# LightingModule.net
KiCad netlist of a schematic drawn in EAGLE
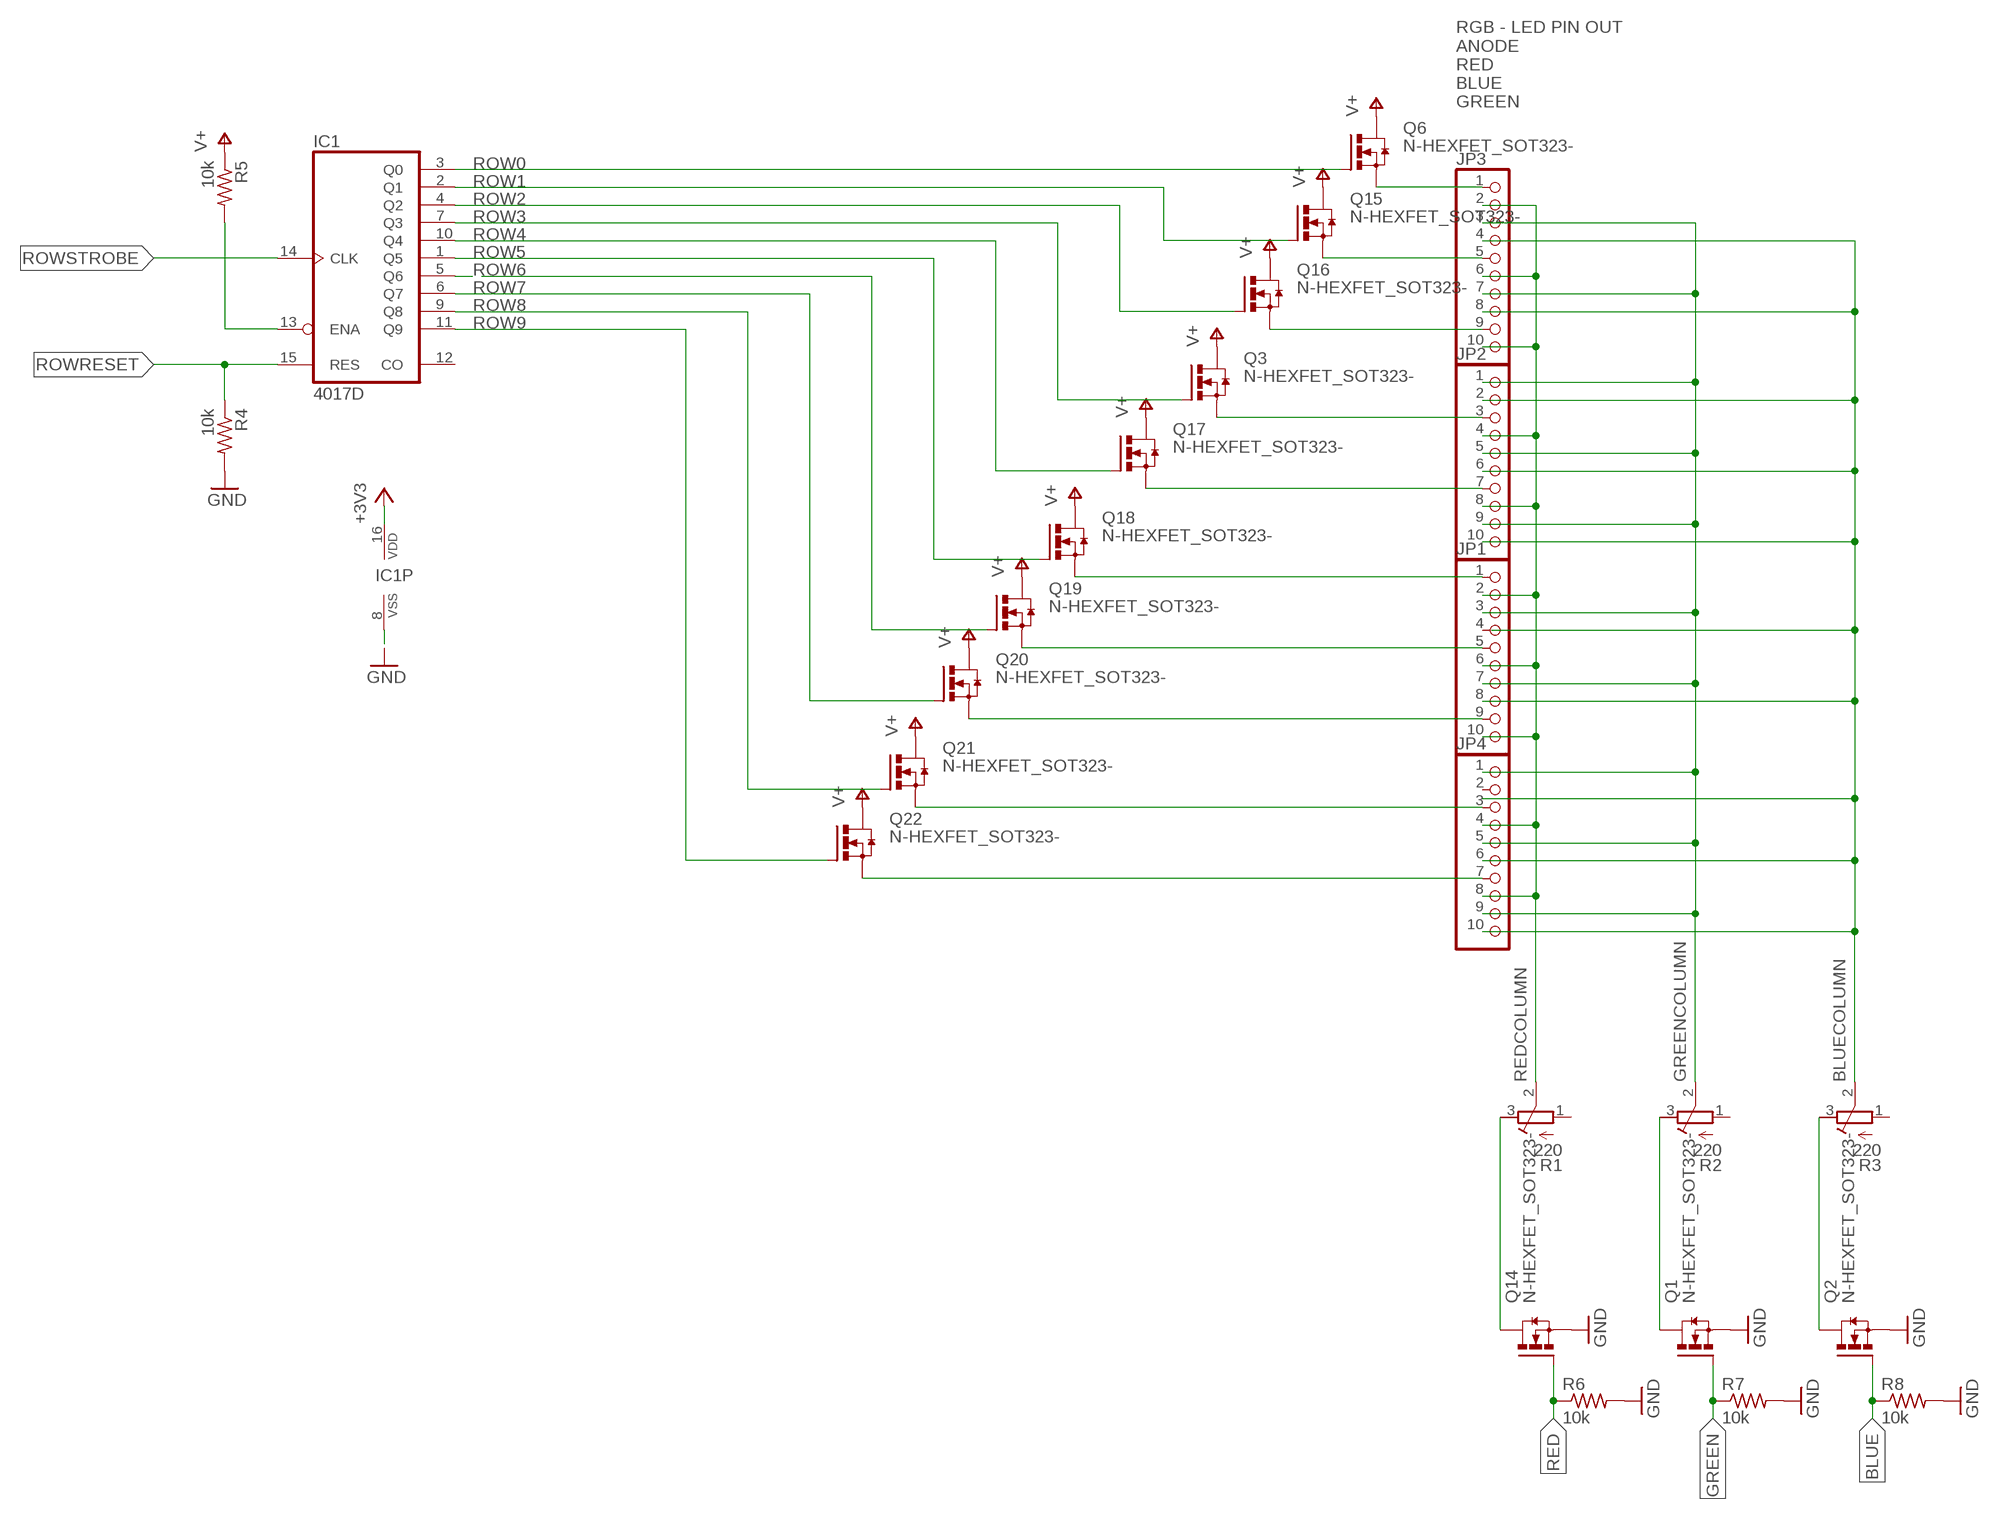
[diagram p0: schematic, sheet 1]

(export (version "E")
  (design (tool "Eeschema 10.0.6"))
  (components
    (comp (ref "IC1")
      (value "4017D")
      (footprint "eagle-import:SO16")
      (libsource (lib "eagle-import") (part "4017D"))
    )
    (comp (ref "JP1")
      (value "PINHD-1X10/90")
      (footprint "eagle-import:1X10_90")
      (libsource (lib "eagle-import") (part "PINHD-1X10/90"))
    )
    (comp (ref "JP2")
      (value "PINHD-1X10/90")
      (footprint "eagle-import:1X10_90")
      (libsource (lib "eagle-import") (part "PINHD-1X10/90"))
    )
    (comp (ref "JP3")
      (value "PINHD-1X10/90")
      (footprint "eagle-import:1X10_90")
      (libsource (lib "eagle-import") (part "PINHD-1X10/90"))
    )
    (comp (ref "JP4")
      (value "PINHD-1X10/90")
      (footprint "eagle-import:1X10_90")
      (libsource (lib "eagle-import") (part "PINHD-1X10/90"))
    )
    (comp (ref "Q1")
      (value "N-HEXFET_SOT323-")
      (footprint "eagle-import:SOT223")
      (libsource (lib "eagle-import") (part "N-HEXFET_?-SOT323"))
    )
    (comp (ref "Q2")
      (value "N-HEXFET_SOT323-")
      (footprint "eagle-import:SOT223")
      (libsource (lib "eagle-import") (part "N-HEXFET_?-SOT323"))
    )
    (comp (ref "Q3")
      (value "N-HEXFET_SOT323-")
      (footprint "eagle-import:SOT223")
      (libsource (lib "eagle-import") (part "N-HEXFET_?-SOT323"))
    )
    (comp (ref "Q6")
      (value "N-HEXFET_SOT323-")
      (footprint "eagle-import:SOT223")
      (libsource (lib "eagle-import") (part "N-HEXFET_?-SOT323"))
    )
    (comp (ref "Q14")
      (value "N-HEXFET_SOT323-")
      (footprint "eagle-import:SOT223")
      (libsource (lib "eagle-import") (part "N-HEXFET_?-SOT323"))
    )
    (comp (ref "Q15")
      (value "N-HEXFET_SOT323-")
      (footprint "eagle-import:SOT223")
      (libsource (lib "eagle-import") (part "N-HEXFET_?-SOT323"))
    )
    (comp (ref "Q16")
      (value "N-HEXFET_SOT323-")
      (footprint "eagle-import:SOT223")
      (libsource (lib "eagle-import") (part "N-HEXFET_?-SOT323"))
    )
    (comp (ref "Q17")
      (value "N-HEXFET_SOT323-")
      (footprint "eagle-import:SOT223")
      (libsource (lib "eagle-import") (part "N-HEXFET_?-SOT323"))
    )
    (comp (ref "Q18")
      (value "N-HEXFET_SOT323-")
      (footprint "eagle-import:SOT223")
      (libsource (lib "eagle-import") (part "N-HEXFET_?-SOT323"))
    )
    (comp (ref "Q19")
      (value "N-HEXFET_SOT323-")
      (footprint "eagle-import:SOT223")
      (libsource (lib "eagle-import") (part "N-HEXFET_?-SOT323"))
    )
    (comp (ref "Q20")
      (value "N-HEXFET_SOT323-")
      (footprint "eagle-import:SOT223")
      (libsource (lib "eagle-import") (part "N-HEXFET_?-SOT323"))
    )
    (comp (ref "Q21")
      (value "N-HEXFET_SOT323-")
      (footprint "eagle-import:SOT223")
      (libsource (lib "eagle-import") (part "N-HEXFET_?-SOT323"))
    )
    (comp (ref "Q22")
      (value "N-HEXFET_SOT323-")
      (footprint "eagle-import:SOT223")
      (libsource (lib "eagle-import") (part "N-HEXFET_?-SOT323"))
    )
    (comp (ref "R1")
      (value "220")
      (footprint "eagle-import:RTRIM3374")
      (libsource (lib "eagle-import") (part "R-TRIMM3374"))
    )
    (comp (ref "R2")
      (value "220")
      (footprint "eagle-import:RTRIM3374")
      (libsource (lib "eagle-import") (part "R-TRIMM3374"))
    )
    (comp (ref "R3")
      (value "220")
      (footprint "eagle-import:RTRIM3374")
      (libsource (lib "eagle-import") (part "R-TRIMM3374"))
    )
    (comp (ref "R4")
      (value "10k")
      (footprint "eagle-import:M0805")
      (libsource (lib "eagle-import") (part "R-US_M0805"))
    )
    (comp (ref "R5")
      (value "10k")
      (footprint "eagle-import:M0805")
      (libsource (lib "eagle-import") (part "R-US_M0805"))
    )
    (comp (ref "R6")
      (value "10k")
      (footprint "eagle-import:M0805")
      (libsource (lib "eagle-import") (part "R-US_M0805"))
    )
    (comp (ref "R7")
      (value "10k")
      (footprint "eagle-import:M0805")
      (libsource (lib "eagle-import") (part "R-US_M0805"))
    )
    (comp (ref "R8")
      (value "10k")
      (footprint "eagle-import:M0805")
      (libsource (lib "eagle-import") (part "R-US_M0805"))
    )
  )
  (nets
    (net (code "1") (name "+3V3") (class "Default")
      (node (ref "IC1") (pin "16") (pinfunction "VDD_16") (pintype "power_in"))
    )
    (net (code "2") (name "/BLUECOLUMN") (class "Default")
      (node (ref "JP1") (pin "8") (pinfunction "8_8") (pintype "passive"))
      (node (ref "JP2") (pin "10") (pinfunction "10_10") (pintype "passive"))
      (node (ref "JP2") (pin "2") (pinfunction "2_2") (pintype "passive"))
      (node (ref "JP2") (pin "6") (pinfunction "6_6") (pintype "passive"))
      (node (ref "JP3") (pin "4") (pinfunction "4_4") (pintype "passive"))
      (node (ref "JP3") (pin "8") (pinfunction "8_8") (pintype "passive"))
      (node (ref "JP4") (pin "10") (pinfunction "10_10") (pintype "passive"))
      (node (ref "JP4") (pin "6") (pinfunction "6_6") (pintype "passive"))
      (node (ref "R3") (pin "2") (pinfunction "S_2") (pintype "passive"))
    )
    (net (code "3") (name "/GREENCOLUMN") (class "Default")
      (node (ref "JP1") (pin "3") (pinfunction "3_3") (pintype "passive"))
      (node (ref "JP1") (pin "7") (pinfunction "7_7") (pintype "passive"))
      (node (ref "JP2") (pin "1") (pinfunction "1_1") (pintype "passive"))
      (node (ref "JP2") (pin "5") (pinfunction "5_5") (pintype "passive"))
      (node (ref "JP2") (pin "9") (pinfunction "9_9") (pintype "passive"))
      (node (ref "JP3") (pin "3") (pinfunction "3_3") (pintype "passive"))
      (node (ref "JP3") (pin "7") (pinfunction "7_7") (pintype "passive"))
      (node (ref "JP4") (pin "1") (pinfunction "1_1") (pintype "passive"))
      (node (ref "JP4") (pin "5") (pinfunction "5_5") (pintype "passive"))
      (node (ref "JP4") (pin "9") (pinfunction "9_9") (pintype "passive"))
      (node (ref "R2") (pin "2") (pinfunction "S_2") (pintype "passive"))
    )
    (net (code "4") (name "/REDCOLUMN") (class "Default")
      (node (ref "JP1") (pin "10") (pinfunction "10_10") (pintype "passive"))
      (node (ref "JP1") (pin "2") (pinfunction "2_2") (pintype "passive"))
      (node (ref "JP1") (pin "6") (pinfunction "6_6") (pintype "passive"))
      (node (ref "JP2") (pin "4") (pinfunction "4_4") (pintype "passive"))
      (node (ref "JP2") (pin "8") (pinfunction "8_8") (pintype "passive"))
      (node (ref "JP3") (pin "10") (pinfunction "10_10") (pintype "passive"))
      (node (ref "JP3") (pin "2") (pinfunction "2_2") (pintype "passive"))
      (node (ref "JP3") (pin "6") (pinfunction "6_6") (pintype "passive"))
      (node (ref "JP4") (pin "4") (pinfunction "4_4") (pintype "passive"))
      (node (ref "JP4") (pin "8") (pinfunction "8_8") (pintype "passive"))
      (node (ref "R1") (pin "2") (pinfunction "S_2") (pintype "passive"))
    )
    (net (code "5") (name "/ROW0") (class "Default")
      (node (ref "IC1") (pin "3") (pinfunction "Q0_3") (pintype "output"))
      (node (ref "Q6") (pin "1") (pinfunction "G_1") (pintype "passive"))
    )
    (net (code "6") (name "/ROW1") (class "Default")
      (node (ref "IC1") (pin "2") (pinfunction "Q1_2") (pintype "output"))
      (node (ref "Q15") (pin "1") (pinfunction "G_1") (pintype "passive"))
    )
    (net (code "7") (name "/ROW2") (class "Default")
      (node (ref "IC1") (pin "4") (pinfunction "Q2_4") (pintype "output"))
      (node (ref "Q16") (pin "1") (pinfunction "G_1") (pintype "passive"))
    )
    (net (code "8") (name "/ROW3") (class "Default")
      (node (ref "IC1") (pin "7") (pinfunction "Q3_7") (pintype "output"))
      (node (ref "Q3") (pin "1") (pinfunction "G_1") (pintype "passive"))
    )
    (net (code "9") (name "/ROW4") (class "Default")
      (node (ref "IC1") (pin "10") (pinfunction "Q4_10") (pintype "output"))
      (node (ref "Q17") (pin "1") (pinfunction "G_1") (pintype "passive"))
    )
    (net (code "10") (name "/ROW5") (class "Default")
      (node (ref "IC1") (pin "1") (pinfunction "Q5_1") (pintype "output"))
      (node (ref "Q18") (pin "1") (pinfunction "G_1") (pintype "passive"))
    )
    (net (code "11") (name "/ROW6") (class "Default")
      (node (ref "IC1") (pin "5") (pinfunction "Q6_5") (pintype "output"))
    )
    (net (code "12") (name "/ROW7") (class "Default")
      (node (ref "IC1") (pin "6") (pinfunction "Q7_6") (pintype "output"))
      (node (ref "Q20") (pin "1") (pinfunction "G_1") (pintype "passive"))
    )
    (net (code "13") (name "/ROW8") (class "Default")
      (node (ref "IC1") (pin "9") (pinfunction "Q8_9") (pintype "output"))
      (node (ref "Q21") (pin "1") (pinfunction "G_1") (pintype "passive"))
    )
    (net (code "14") (name "/ROW9") (class "Default")
      (node (ref "IC1") (pin "11") (pinfunction "Q9_11") (pintype "output"))
      (node (ref "Q22") (pin "1") (pinfunction "G_1") (pintype "passive"))
    )
    (net (code "15") (name "BLUE") (class "Default")
      (node (ref "Q2") (pin "1") (pinfunction "G_1") (pintype "passive"))
      (node (ref "R8") (pin "1") (pinfunction "1_1") (pintype "passive"))
    )
    (net (code "16") (name "GND") (class "Default")
      (node (ref "IC1") (pin "8") (pinfunction "VSS_8") (pintype "power_in"))
      (node (ref "Q1") (pin "3") (pinfunction "S_3") (pintype "passive"))
      (node (ref "Q14") (pin "3") (pinfunction "S_3") (pintype "passive"))
      (node (ref "Q2") (pin "3") (pinfunction "S_3") (pintype "passive"))
      (node (ref "R4") (pin "2") (pinfunction "2_2") (pintype "passive"))
      (node (ref "R6") (pin "2") (pinfunction "2_2") (pintype "passive"))
      (node (ref "R7") (pin "2") (pinfunction "2_2") (pintype "passive"))
      (node (ref "R8") (pin "2") (pinfunction "2_2") (pintype "passive"))
    )
    (net (code "17") (name "GREEN") (class "Default")
      (node (ref "Q1") (pin "1") (pinfunction "G_1") (pintype "passive"))
      (node (ref "R7") (pin "1") (pinfunction "1_1") (pintype "passive"))
    )
    (net (code "18") (name "Net-(IC1A-ENA)") (class "Default")
      (node (ref "IC1") (pin "13") (pinfunction "ENA_13") (pintype "input"))
      (node (ref "R5") (pin "2") (pinfunction "2_2") (pintype "passive"))
    )
    (net (code "19") (name "Net-(Q1-D)") (class "Default")
      (node (ref "Q1") (pin "4") (pinfunction "D_4") (pintype "passive"))
      (node (ref "R2") (pin "3") (pinfunction "A_3") (pintype "passive"))
    )
    (net (code "20") (name "Net-(Q2-D)") (class "Default")
      (node (ref "Q2") (pin "4") (pinfunction "D_4") (pintype "passive"))
      (node (ref "R3") (pin "3") (pinfunction "A_3") (pintype "passive"))
    )
    (net (code "21") (name "Net-(Q3-S)") (class "Default")
      (node (ref "JP2") (pin "3") (pinfunction "3_3") (pintype "passive"))
      (node (ref "Q3") (pin "3") (pinfunction "S_3") (pintype "passive"))
    )
    (net (code "22") (name "Net-(Q6-S)") (class "Default")
      (node (ref "JP3") (pin "1") (pinfunction "1_1") (pintype "passive"))
      (node (ref "Q6") (pin "3") (pinfunction "S_3") (pintype "passive"))
    )
    (net (code "23") (name "Net-(Q14-D)") (class "Default")
      (node (ref "Q14") (pin "4") (pinfunction "D_4") (pintype "passive"))
      (node (ref "R1") (pin "3") (pinfunction "A_3") (pintype "passive"))
    )
    (net (code "24") (name "Net-(Q15-S)") (class "Default")
      (node (ref "JP3") (pin "5") (pinfunction "5_5") (pintype "passive"))
      (node (ref "Q15") (pin "3") (pinfunction "S_3") (pintype "passive"))
    )
    (net (code "25") (name "Net-(Q16-S)") (class "Default")
      (node (ref "JP3") (pin "9") (pinfunction "9_9") (pintype "passive"))
      (node (ref "Q16") (pin "3") (pinfunction "S_3") (pintype "passive"))
    )
    (net (code "26") (name "Net-(Q17-S)") (class "Default")
      (node (ref "JP2") (pin "7") (pinfunction "7_7") (pintype "passive"))
      (node (ref "Q17") (pin "3") (pinfunction "S_3") (pintype "passive"))
    )
    (net (code "27") (name "Net-(Q18-S)") (class "Default")
      (node (ref "JP1") (pin "1") (pinfunction "1_1") (pintype "passive"))
      (node (ref "Q18") (pin "3") (pinfunction "S_3") (pintype "passive"))
    )
    (net (code "28") (name "Net-(Q19-S)") (class "Default")
      (node (ref "JP1") (pin "5") (pinfunction "5_5") (pintype "passive"))
      (node (ref "Q19") (pin "3") (pinfunction "S_3") (pintype "passive"))
    )
    (net (code "29") (name "Net-(Q20-S)") (class "Default")
      (node (ref "JP1") (pin "9") (pinfunction "9_9") (pintype "passive"))
      (node (ref "Q20") (pin "3") (pinfunction "S_3") (pintype "passive"))
    )
    (net (code "30") (name "Net-(Q21-S)") (class "Default")
      (node (ref "JP4") (pin "3") (pinfunction "3_3") (pintype "passive"))
      (node (ref "Q21") (pin "3") (pinfunction "S_3") (pintype "passive"))
    )
    (net (code "31") (name "Net-(Q22-S)") (class "Default")
      (node (ref "JP4") (pin "7") (pinfunction "7_7") (pintype "passive"))
      (node (ref "Q22") (pin "3") (pinfunction "S_3") (pintype "passive"))
    )
    (net (code "32") (name "RED") (class "Default")
      (node (ref "Q14") (pin "1") (pinfunction "G_1") (pintype "passive"))
      (node (ref "R6") (pin "1") (pinfunction "1_1") (pintype "passive"))
    )
    (net (code "33") (name "ROWRESET") (class "Default")
      (node (ref "IC1") (pin "15") (pinfunction "RES_15") (pintype "input"))
      (node (ref "R4") (pin "1") (pinfunction "1_1") (pintype "passive"))
    )
    (net (code "34") (name "ROWSTROBE") (class "Default")
      (node (ref "IC1") (pin "14") (pinfunction "CLK_14") (pintype "input"))
    )
    (net (code "35") (name "V+") (class "Default")
      (node (ref "Q15") (pin "4") (pinfunction "D_4") (pintype "passive"))
      (node (ref "Q16") (pin "4") (pinfunction "D_4") (pintype "passive"))
      (node (ref "Q17") (pin "4") (pinfunction "D_4") (pintype "passive"))
      (node (ref "Q18") (pin "4") (pinfunction "D_4") (pintype "passive"))
      (node (ref "Q19") (pin "4") (pinfunction "D_4") (pintype "passive"))
      (node (ref "Q20") (pin "4") (pinfunction "D_4") (pintype "passive"))
      (node (ref "Q21") (pin "4") (pinfunction "D_4") (pintype "passive"))
      (node (ref "Q22") (pin "4") (pinfunction "D_4") (pintype "passive"))
      (node (ref "Q3") (pin "4") (pinfunction "D_4") (pintype "passive"))
      (node (ref "Q6") (pin "4") (pinfunction "D_4") (pintype "passive"))
      (node (ref "R5") (pin "1") (pinfunction "1_1") (pintype "passive"))
    )
    (net (code "36") (name "unconnected-(IC1A-CO-Pad12)") (class "Default")
      (node (ref "IC1") (pin "12") (pinfunction "CO_12") (pintype "output"))
    )
    (net (code "37") (name "unconnected-(JP1-Pad4)") (class "Default")
      (node (ref "JP1") (pin "4") (pinfunction "4_4") (pintype "passive"))
    )
    (net (code "38") (name "unconnected-(JP4-Pad2)") (class "Default")
      (node (ref "JP4") (pin "2") (pinfunction "2_2") (pintype "passive"))
    )
    (net (code "39") (name "unconnected-(Q19-G-Pad1)") (class "Default")
      (node (ref "Q19") (pin "1") (pinfunction "G_1") (pintype "passive"))
    )
    (net (code "40") (name "unconnected-(R1-E-Pad1)") (class "Default")
      (node (ref "R1") (pin "1") (pinfunction "E_1") (pintype "passive"))
    )
    (net (code "41") (name "unconnected-(R2-E-Pad1)") (class "Default")
      (node (ref "R2") (pin "1") (pinfunction "E_1") (pintype "passive"))
    )
    (net (code "42") (name "unconnected-(R3-E-Pad1)") (class "Default")
      (node (ref "R3") (pin "1") (pinfunction "E_1") (pintype "passive"))
    )
  )
)
